# Super-Regenerative-Airband-1Transistor-K.net
KiCad netlist of a schematic drawn in EAGLE
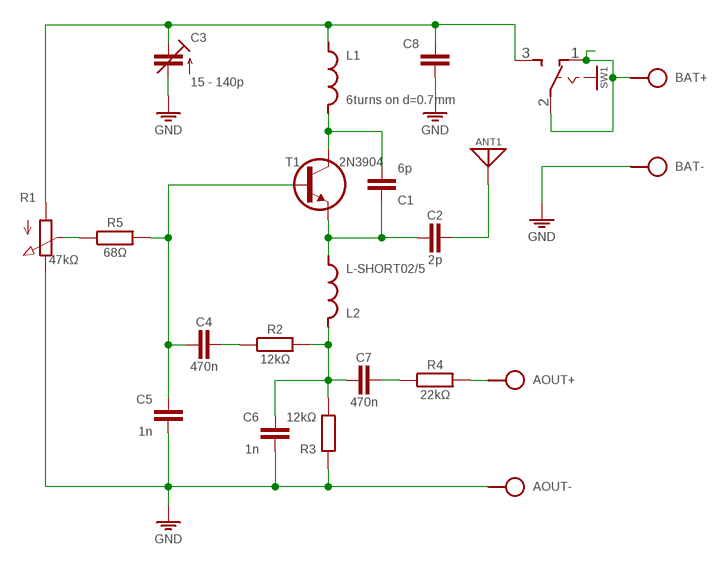
[diagram p0: schematic, sheet 1]

(export (version "E")
  (design (tool "Eeschema 10.0.6"))
  (components
    (comp (ref "ANT1")
      (value "ANT")
      (footprint "eagle-import:SPAD")
      (libsource (lib "eagle-import") (part "ANT"))
    )
    (comp (ref "AOUT+")
      (value "SPAD")
      (footprint "eagle-import:SPAD")
      (libsource (lib "eagle-import") (part "SPAD"))
    )
    (comp (ref "AOUT-")
      (value "SPAD")
      (footprint "eagle-import:SPAD")
      (libsource (lib "eagle-import") (part "SPAD"))
    )
    (comp (ref "BAT+")
      (value "SPAD")
      (footprint "eagle-import:SPAD")
      (libsource (lib "eagle-import") (part "SPAD"))
    )
    (comp (ref "BAT-")
      (value "SPAD")
      (footprint "eagle-import:SPAD")
      (libsource (lib "eagle-import") (part "SPAD"))
    )
    (comp (ref "C1")
      (value "6p")
      (footprint "eagle-import:C050-020X036")
      (libsource (lib "eagle-import") (part "C050-020X036"))
    )
    (comp (ref "C2")
      (value "2p")
      (footprint "eagle-import:C025-015X024")
      (libsource (lib "eagle-import") (part "C025-015X024"))
    )
    (comp (ref "C3")
      (value "15 - 140p")
      (footprint "eagle-import:TRIM-2222-808")
      (libsource (lib "eagle-import") (part "C-TR-PH201272222-808-2PINB"))
    )
    (comp (ref "C4")
      (value "470n")
      (footprint "eagle-import:C050-020X036")
      (libsource (lib "eagle-import") (part "C050-020X036"))
    )
    (comp (ref "C5")
      (value "1n")
      (footprint "eagle-import:C025-020X036")
      (libsource (lib "eagle-import") (part "C025-020X036"))
    )
    (comp (ref "C6")
      (value "1n")
      (footprint "eagle-import:C050-020X036")
      (libsource (lib "eagle-import") (part "C050-020X036"))
    )
    (comp (ref "C7")
      (value "470n")
      (footprint "eagle-import:C050-020X036")
      (libsource (lib "eagle-import") (part "C050-020X036"))
    )
    (comp (ref "C8")
      (value "C050-025X075")
      (footprint "eagle-import:C050-025X075")
      (libsource (lib "eagle-import") (part "C050-025X075"))
    )
    (comp (ref "L1")
      (value "6turns on d=0.7mm")
      (footprint "eagle-import:L-04_7V-X")
      (libsource (lib "eagle-import") (part "L-SHORTL-04/7V-X"))
    )
    (comp (ref "L2")
      (value "L-SHORT02/5")
      (footprint "eagle-import:L-04-5_6V")
      (libsource (lib "eagle-import") (part "L-SHORT04-5/5V"))
    )
    (comp (ref "R1")
      (value "47kΩ")
      (footprint "eagle-import:POT")
      (libsource (lib "eagle-import") (part "POT"))
    )
    (comp (ref "R2")
      (value "12kΩ")
      (footprint "eagle-import:0202_7")
      (libsource (lib "eagle-import") (part "R-H0202/7"))
    )
    (comp (ref "R3")
      (value "12kΩ")
      (footprint "eagle-import:0202_7")
      (libsource (lib "eagle-import") (part "R0202/7"))
    )
    (comp (ref "R4")
      (value "22kΩ")
      (footprint "eagle-import:0202_7")
      (libsource (lib "eagle-import") (part "R-H0202/7"))
    )
    (comp (ref "R5")
      (value "68Ω")
      (footprint "eagle-import:0202_7")
      (libsource (lib "eagle-import") (part "R-H0202/7"))
    )
    (comp (ref "SW1")
      (value "SL-SW-1P-2T-H")
      (footprint "eagle-import:SLSW-1P2T-H")
      (libsource (lib "eagle-import") (part "SL-SW-1P-2T-H"))
    )
    (comp (ref "T1")
      (value "2N3904")
      (footprint "eagle-import:TO92")
      (libsource (lib "eagle-import") (part "2N3904"))
    )
  )
  (nets
    (net (code "1") (name "GND") (class "Default")
      (node (ref "AOUT-") (pin "1") (pinfunction "P$1_1") (pintype "bidirectional"))
      (node (ref "BAT-") (pin "1") (pinfunction "P$1_1") (pintype "bidirectional"))
      (node (ref "C3") (pin "2") (pinfunction "A_2") (pintype "passive"))
      (node (ref "C5") (pin "2") (pinfunction "2_2") (pintype "passive"))
      (node (ref "C6") (pin "2") (pinfunction "2_2") (pintype "passive"))
      (node (ref "C8") (pin "2") (pinfunction "2_2") (pintype "passive"))
      (node (ref "R1") (pin "3") (pinfunction "E_3") (pintype "passive"))
      (node (ref "R3") (pin "2") (pinfunction "2_2") (pintype "passive"))
    )
    (net (code "2") (name "Net-(ANT1-Pad1)") (class "Default")
      (node (ref "ANT1") (pin "1") (pinfunction "1_1") (pintype "output"))
      (node (ref "C2") (pin "1") (pinfunction "1_1") (pintype "passive"))
    )
    (net (code "3") (name "Net-(AOUT+-P$1)") (class "Default")
      (node (ref "AOUT+") (pin "1") (pinfunction "P$1_1") (pintype "bidirectional"))
      (node (ref "R4") (pin "2") (pinfunction "2_2") (pintype "passive"))
    )
    (net (code "4") (name "Net-(BAT+-P$1)") (class "Default")
      (node (ref "BAT+") (pin "1") (pinfunction "P$1_1") (pintype "bidirectional"))
      (node (ref "SW1") (pin "1") (pinfunction "O_1") (pintype "passive"))
      (node (ref "SW1") (pin "2") (pinfunction "P_2") (pintype "passive"))
    )
    (net (code "5") (name "Net-(C3-E)") (class "Default")
      (node (ref "C3") (pin "3") (pinfunction "E_3") (pintype "passive"))
      (node (ref "C8") (pin "1") (pinfunction "1_1") (pintype "passive"))
      (node (ref "L1") (pin "2") (pinfunction "2_2") (pintype "passive"))
      (node (ref "R1") (pin "1") (pinfunction "A_1") (pintype "passive"))
      (node (ref "SW1") (pin "3") (pinfunction "S_3") (pintype "passive"))
    )
    (net (code "6") (name "Net-(C4-Pad1)") (class "Default")
      (node (ref "C4") (pin "1") (pinfunction "1_1") (pintype "passive"))
      (node (ref "R2") (pin "1") (pinfunction "1_1") (pintype "passive"))
    )
    (net (code "7") (name "Net-(C6-Pad1)") (class "Default")
      (node (ref "C6") (pin "1") (pinfunction "1_1") (pintype "passive"))
      (node (ref "C7") (pin "2") (pinfunction "2_2") (pintype "passive"))
      (node (ref "L2") (pin "2") (pinfunction "2_2") (pintype "passive"))
      (node (ref "R2") (pin "2") (pinfunction "2_2") (pintype "passive"))
      (node (ref "R3") (pin "1") (pinfunction "1_1") (pintype "passive"))
    )
    (net (code "8") (name "Net-(C7-Pad1)") (class "Default")
      (node (ref "C7") (pin "1") (pinfunction "1_1") (pintype "passive"))
      (node (ref "R4") (pin "1") (pinfunction "1_1") (pintype "passive"))
    )
    (net (code "9") (name "Net-(R1-S)") (class "Default")
      (node (ref "R1") (pin "2") (pinfunction "S_2") (pintype "passive"))
      (node (ref "R5") (pin "1") (pinfunction "1_1") (pintype "passive"))
    )
    (net (code "10") (name "Net-(T1-B)") (class "Default")
      (node (ref "C4") (pin "2") (pinfunction "2_2") (pintype "passive"))
      (node (ref "C5") (pin "1") (pinfunction "1_1") (pintype "passive"))
      (node (ref "R5") (pin "2") (pinfunction "2_2") (pintype "passive"))
      (node (ref "T1") (pin "2") (pinfunction "B_2") (pintype "passive"))
    )
    (net (code "11") (name "Net-(T1-C)") (class "Default")
      (node (ref "C1") (pin "2") (pinfunction "2_2") (pintype "passive"))
      (node (ref "L1") (pin "1") (pinfunction "1_1") (pintype "passive"))
      (node (ref "T1") (pin "3") (pinfunction "C_3") (pintype "passive"))
    )
    (net (code "12") (name "Net-(T1-E)") (class "Default")
      (node (ref "C1") (pin "1") (pinfunction "1_1") (pintype "passive"))
      (node (ref "C2") (pin "2") (pinfunction "2_2") (pintype "passive"))
      (node (ref "L2") (pin "1") (pinfunction "1_1") (pintype "passive"))
      (node (ref "T1") (pin "1") (pinfunction "E_1") (pintype "passive"))
    )
  )
)
